# stamp-fixed-smt-mk-1_0.net
KiCad netlist of a schematic drawn in EAGLE
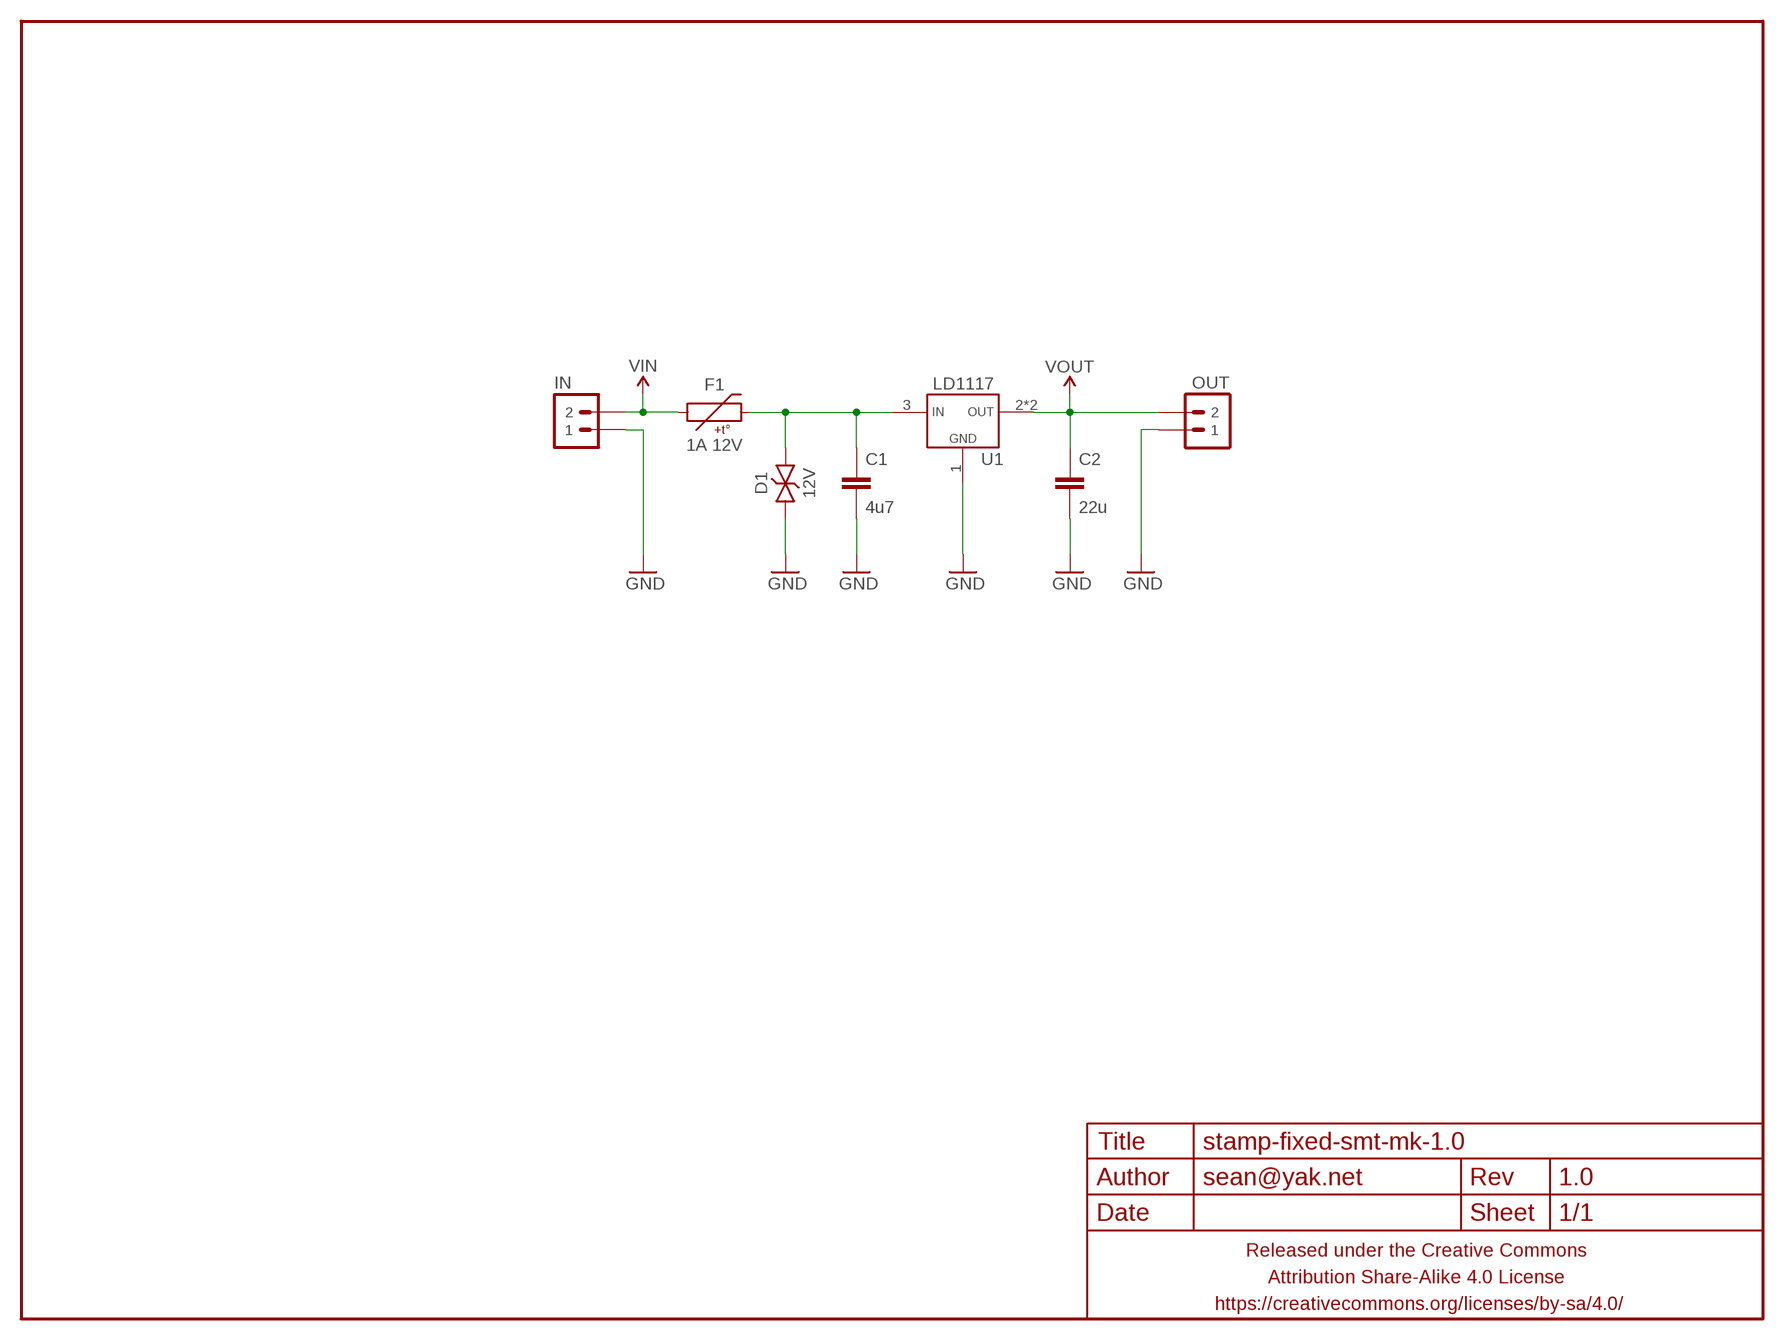
[diagram p0: schematic, sheet 1]

(export (version "E")
  (design (tool "Eeschema 10.0.6"))
  (components
    (comp (ref "C1")
      (value "4u7")
      (footprint "eagle-import:C0805-TIGHTER")
      (libsource (lib "eagle-import") (part "CAPACITOR-CERAMICC0805-TIGHTER"))
    )
    (comp (ref "C2")
      (value "22u")
      (footprint "eagle-import:C0805-TIGHTER")
      (libsource (lib "eagle-import") (part "CAPACITOR-CERAMICC0805-TIGHTER"))
    )
    (comp (ref "D1")
      (value "12V")
      (footprint "eagle-import:SOD323-TVS-BIDIR")
      (libsource (lib "eagle-import") (part "TVSSOD323"))
    )
    (comp (ref "F1")
      (value "1A 12V")
      (footprint "eagle-import:PTC-1206")
      (libsource (lib "eagle-import") (part "PTCSMD"))
    )
    (comp (ref "FRAME1")
      (value "FRAME-LETTERNO_PACKAGE")
      (footprint "eagle-import:DUMMY")
      (fields (field (name "DESIGNER") "sean@yak.net") (field (name "VERSION") "1.0"))
      (libsource (lib "eagle-import") (part "FRAME-LETTERNO_PACKAGE"))
    )
    (comp (ref "IN")
      (value "M02PTH-CENTERED-R+")
      (footprint "eagle-import:1X02-CENTER-R+")
      (libsource (lib "eagle-import") (part "M02PTH-CENTERED-R+"))
    )
    (comp (ref "OUT")
      (value "M02PTH-CENTERED-R+")
      (footprint "eagle-import:1X02-CENTER-R+")
      (libsource (lib "eagle-import") (part "M02PTH-CENTERED-R+"))
    )
    (comp (ref "U1")
      (value "LD1117")
      (footprint "eagle-import:SOT223")
      (libsource (lib "eagle-import") (part "VREG_1117SOT223"))
    )
  )
  (nets
    (net (code "1") (name "GND") (class "Default")
      (node (ref "C1") (pin "2") (pinfunction "2_2") (pintype "passive"))
      (node (ref "C2") (pin "2") (pinfunction "2_2") (pintype "passive"))
      (node (ref "D1") (pin "A") (pinfunction "1_A") (pintype "passive"))
      (node (ref "IN") (pin "1") (pinfunction "1_1") (pintype "passive"))
      (node (ref "OUT") (pin "1") (pinfunction "1_1") (pintype "passive"))
      (node (ref "U1") (pin "1") (pinfunction "GND_1") (pintype "bidirectional"))
    )
    (net (code "2") (name "Net-(D1-2)") (class "Default")
      (node (ref "C1") (pin "1") (pinfunction "1_1") (pintype "passive"))
      (node (ref "D1") (pin "C") (pinfunction "2_C") (pintype "passive"))
      (node (ref "F1") (pin "2") (pinfunction "2_2") (pintype "passive"))
      (node (ref "U1") (pin "3") (pinfunction "VIN_3") (pintype "bidirectional"))
    )
    (net (code "3") (name "VIN") (class "Default")
      (node (ref "F1") (pin "1") (pinfunction "1_1") (pintype "passive"))
      (node (ref "IN") (pin "2") (pinfunction "2_2") (pintype "passive"))
    )
    (net (code "4") (name "VOUT") (class "Default")
      (node (ref "C2") (pin "1") (pinfunction "1_1") (pintype "passive"))
      (node (ref "OUT") (pin "2") (pinfunction "2_2") (pintype "passive"))
      (node (ref "U1") (pin "2") (pinfunction "VOUT_2") (pintype "bidirectional"))
      (node (ref "U1") (pin "4") (pinfunction "VOUT_4") (pintype "bidirectional"))
    )
  )
)
